# LB_BIT_o15_UV_LED-v02_rev1.net
KiCad netlist of a schematic drawn in EAGLE
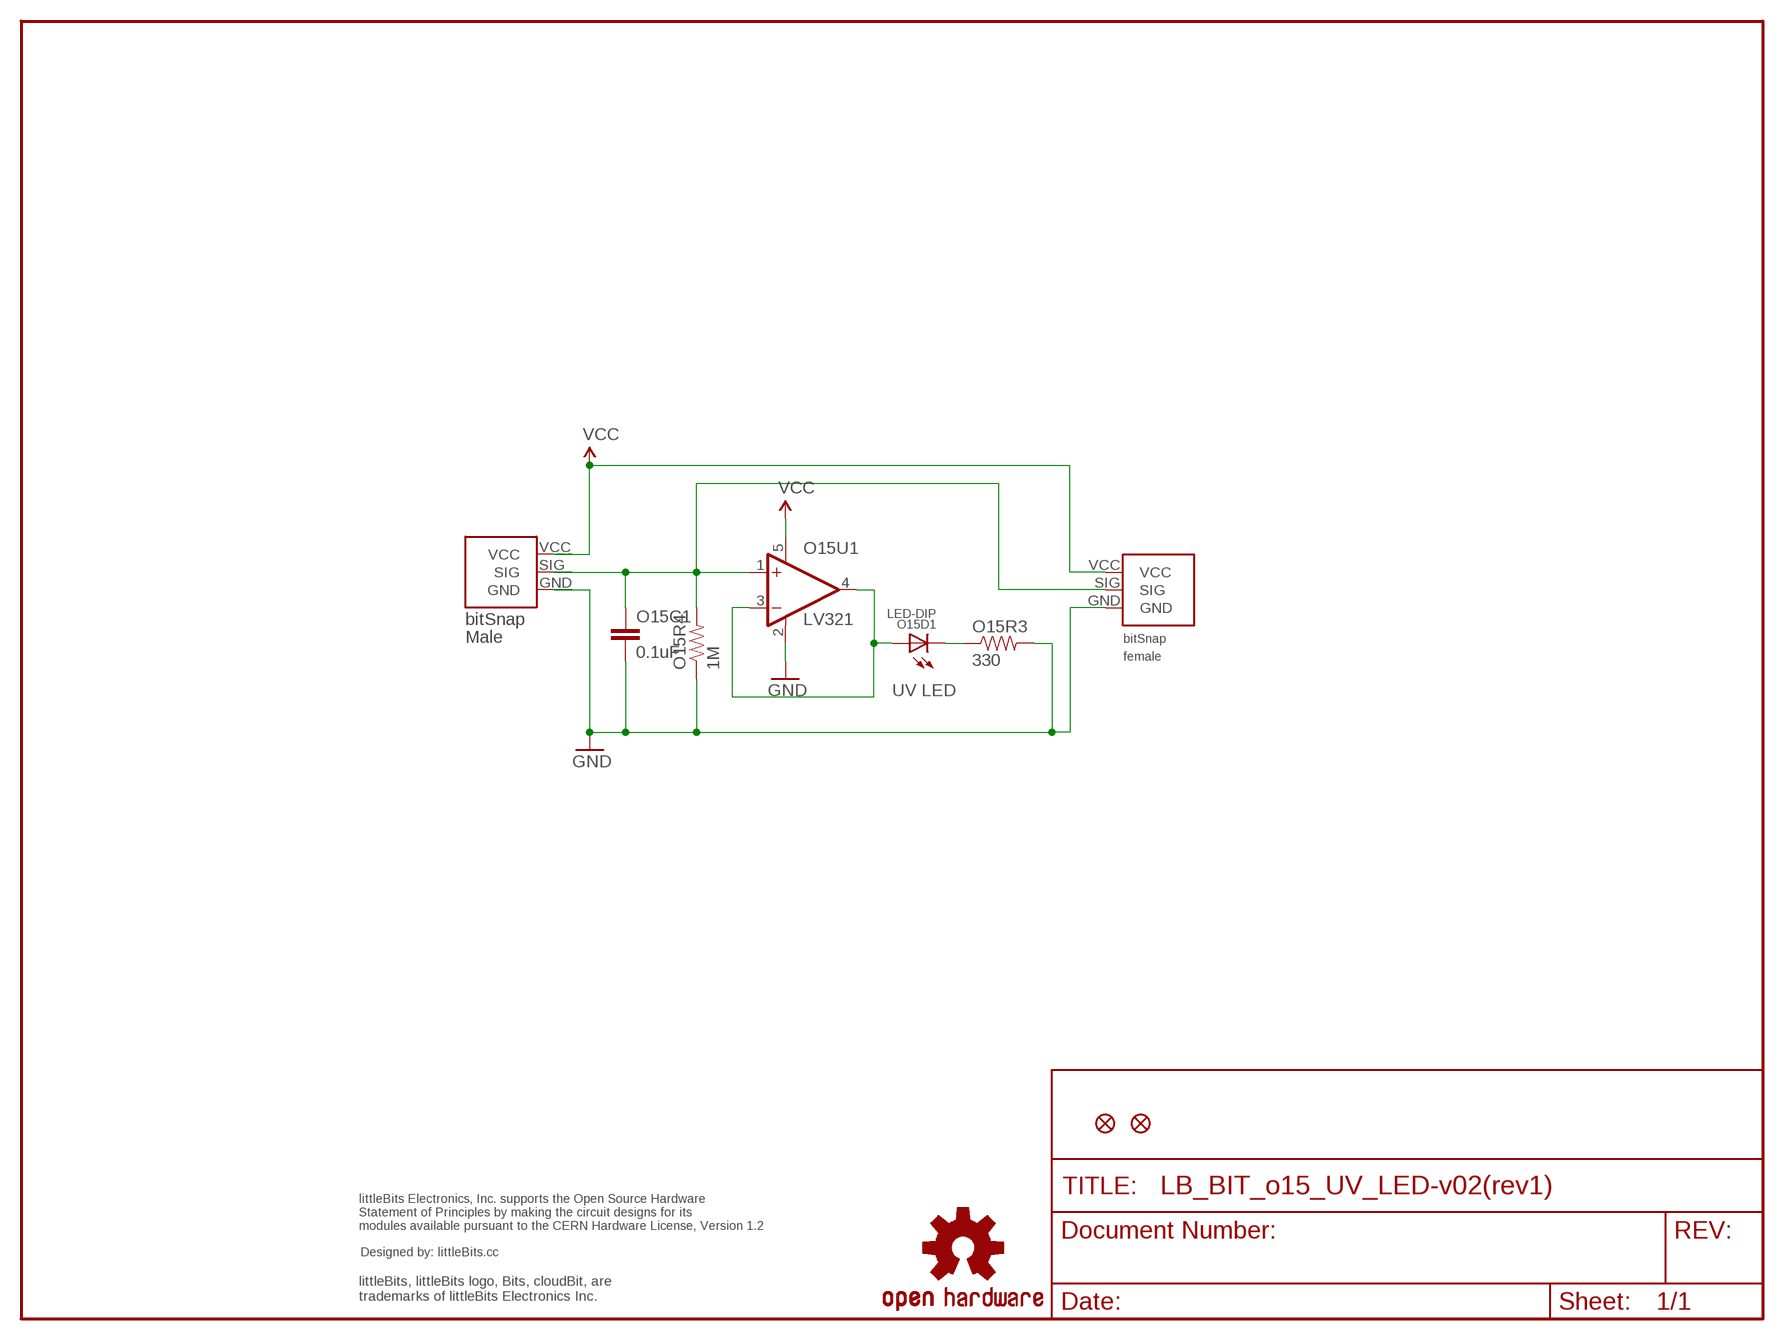
[diagram p0: schematic, sheet 1]

(export (version "E")
  (design (tool "Eeschema 10.0.6"))
  (components
    (comp (ref "O15BSF")
      (value "BITSNAP_FEMALE")
      (footprint "eagle-import:BITSNAP_FEMALE")
      (libsource (lib "eagle-import") (part "BITSNAP_FEMALE"))
    )
    (comp (ref "O15BSM")
      (value "BITSNAP_MALE")
      (footprint "eagle-import:BITSNAP_MALE")
      (libsource (lib "eagle-import") (part "BITSNAP_MALE"))
    )
    (comp (ref "O15C1")
      (value "0.1uF")
      (footprint "eagle-import:0603-CAP")
      (libsource (lib "eagle-import") (part "CAP0603-CAP"))
    )
    (comp (ref "O15D1")
      (value "LED-DIP")
      (footprint "eagle-import:LED-DIP")
      (libsource (lib "eagle-import") (part "LED-DIP"))
    )
    (comp (ref "O15FD1")
      (value "FIDUCIAL1X2.5")
      (footprint "eagle-import:FIDUCIAL-1X2.5")
      (libsource (lib "eagle-import") (part "FIDUCIAL1X2.5"))
    )
    (comp (ref "O15FD2")
      (value "FIDUCIAL1X2.5")
      (footprint "eagle-import:FIDUCIAL-1X2.5")
      (libsource (lib "eagle-import") (part "FIDUCIAL1X2.5"))
    )
    (comp (ref "O15R3")
      (value "330")
      (footprint "eagle-import:0603-RES")
      (libsource (lib "eagle-import") (part "RESISTOR0603-RES"))
    )
    (comp (ref "O15R4")
      (value "1M")
      (footprint "eagle-import:0603-RES")
      (libsource (lib "eagle-import") (part "RESISTOR0603-RES"))
    )
    (comp (ref "O15U1")
      (value "LV321")
      (footprint "eagle-import:SC70-5")
      (libsource (lib "eagle-import") (part "LV321"))
    )
    (comp (ref "U$1")
      (value "OSHWCREDIT")
      (footprint "eagle-import:OSHWCREDIT")
      (libsource (lib "eagle-import") (part "OSHWCREDIT"))
    )
    (comp (ref "U$3")
      (value "OSHW-LOGOL")
      (footprint "eagle-import:OSHW-LOGO-L")
      (libsource (lib "eagle-import") (part "OSHW-LOGOL"))
    )
  )
  (nets
    (net (code "1") (name "GND") (class "Default")
      (node (ref "O15BSF") (pin "GND") (pinfunction "GND_GND") (pintype "bidirectional"))
      (node (ref "O15BSM") (pin "GND") (pinfunction "GND_GND") (pintype "bidirectional"))
      (node (ref "O15C1") (pin "2") (pinfunction "2_2") (pintype "passive"))
      (node (ref "O15R3") (pin "2") (pinfunction "2_2") (pintype "passive"))
      (node (ref "O15R4") (pin "1") (pinfunction "1_1") (pintype "passive"))
      (node (ref "O15U1") (pin "2") (pinfunction "V-_2") (pintype "power_in"))
    )
    (net (code "2") (name "Net-(O15D1-PadC)") (class "Default")
      (node (ref "O15D1") (pin "C") (pinfunction "C_C") (pintype "passive"))
      (node (ref "O15R3") (pin "1") (pinfunction "1_1") (pintype "passive"))
    )
    (net (code "3") (name "Net-(O15U1-+IN)") (class "Default")
      (node (ref "O15BSF") (pin "SIG") (pinfunction "SIG_SIG") (pintype "bidirectional"))
      (node (ref "O15BSM") (pin "SIG") (pinfunction "SIG_SIG") (pintype "bidirectional"))
      (node (ref "O15C1") (pin "1") (pinfunction "1_1") (pintype "passive"))
      (node (ref "O15R4") (pin "2") (pinfunction "2_2") (pintype "passive"))
      (node (ref "O15U1") (pin "1") (pinfunction "+IN_1") (pintype "input"))
    )
    (net (code "4") (name "Net-(O15U1--IN)") (class "Default")
      (node (ref "O15D1") (pin "A") (pinfunction "A_A") (pintype "passive"))
      (node (ref "O15U1") (pin "3") (pinfunction "-IN_3") (pintype "input"))
      (node (ref "O15U1") (pin "4") (pinfunction "OUT_4") (pintype "output"))
    )
    (net (code "5") (name "VCC") (class "Default")
      (node (ref "O15BSF") (pin "VCC") (pinfunction "VCC_VCC") (pintype "bidirectional"))
      (node (ref "O15BSM") (pin "VCC") (pinfunction "VCC_VCC") (pintype "bidirectional"))
      (node (ref "O15U1") (pin "5") (pinfunction "V+_5") (pintype "power_in"))
    )
  )
)
